# antenna_tracker.net
KiCad netlist of a schematic drawn in EAGLE
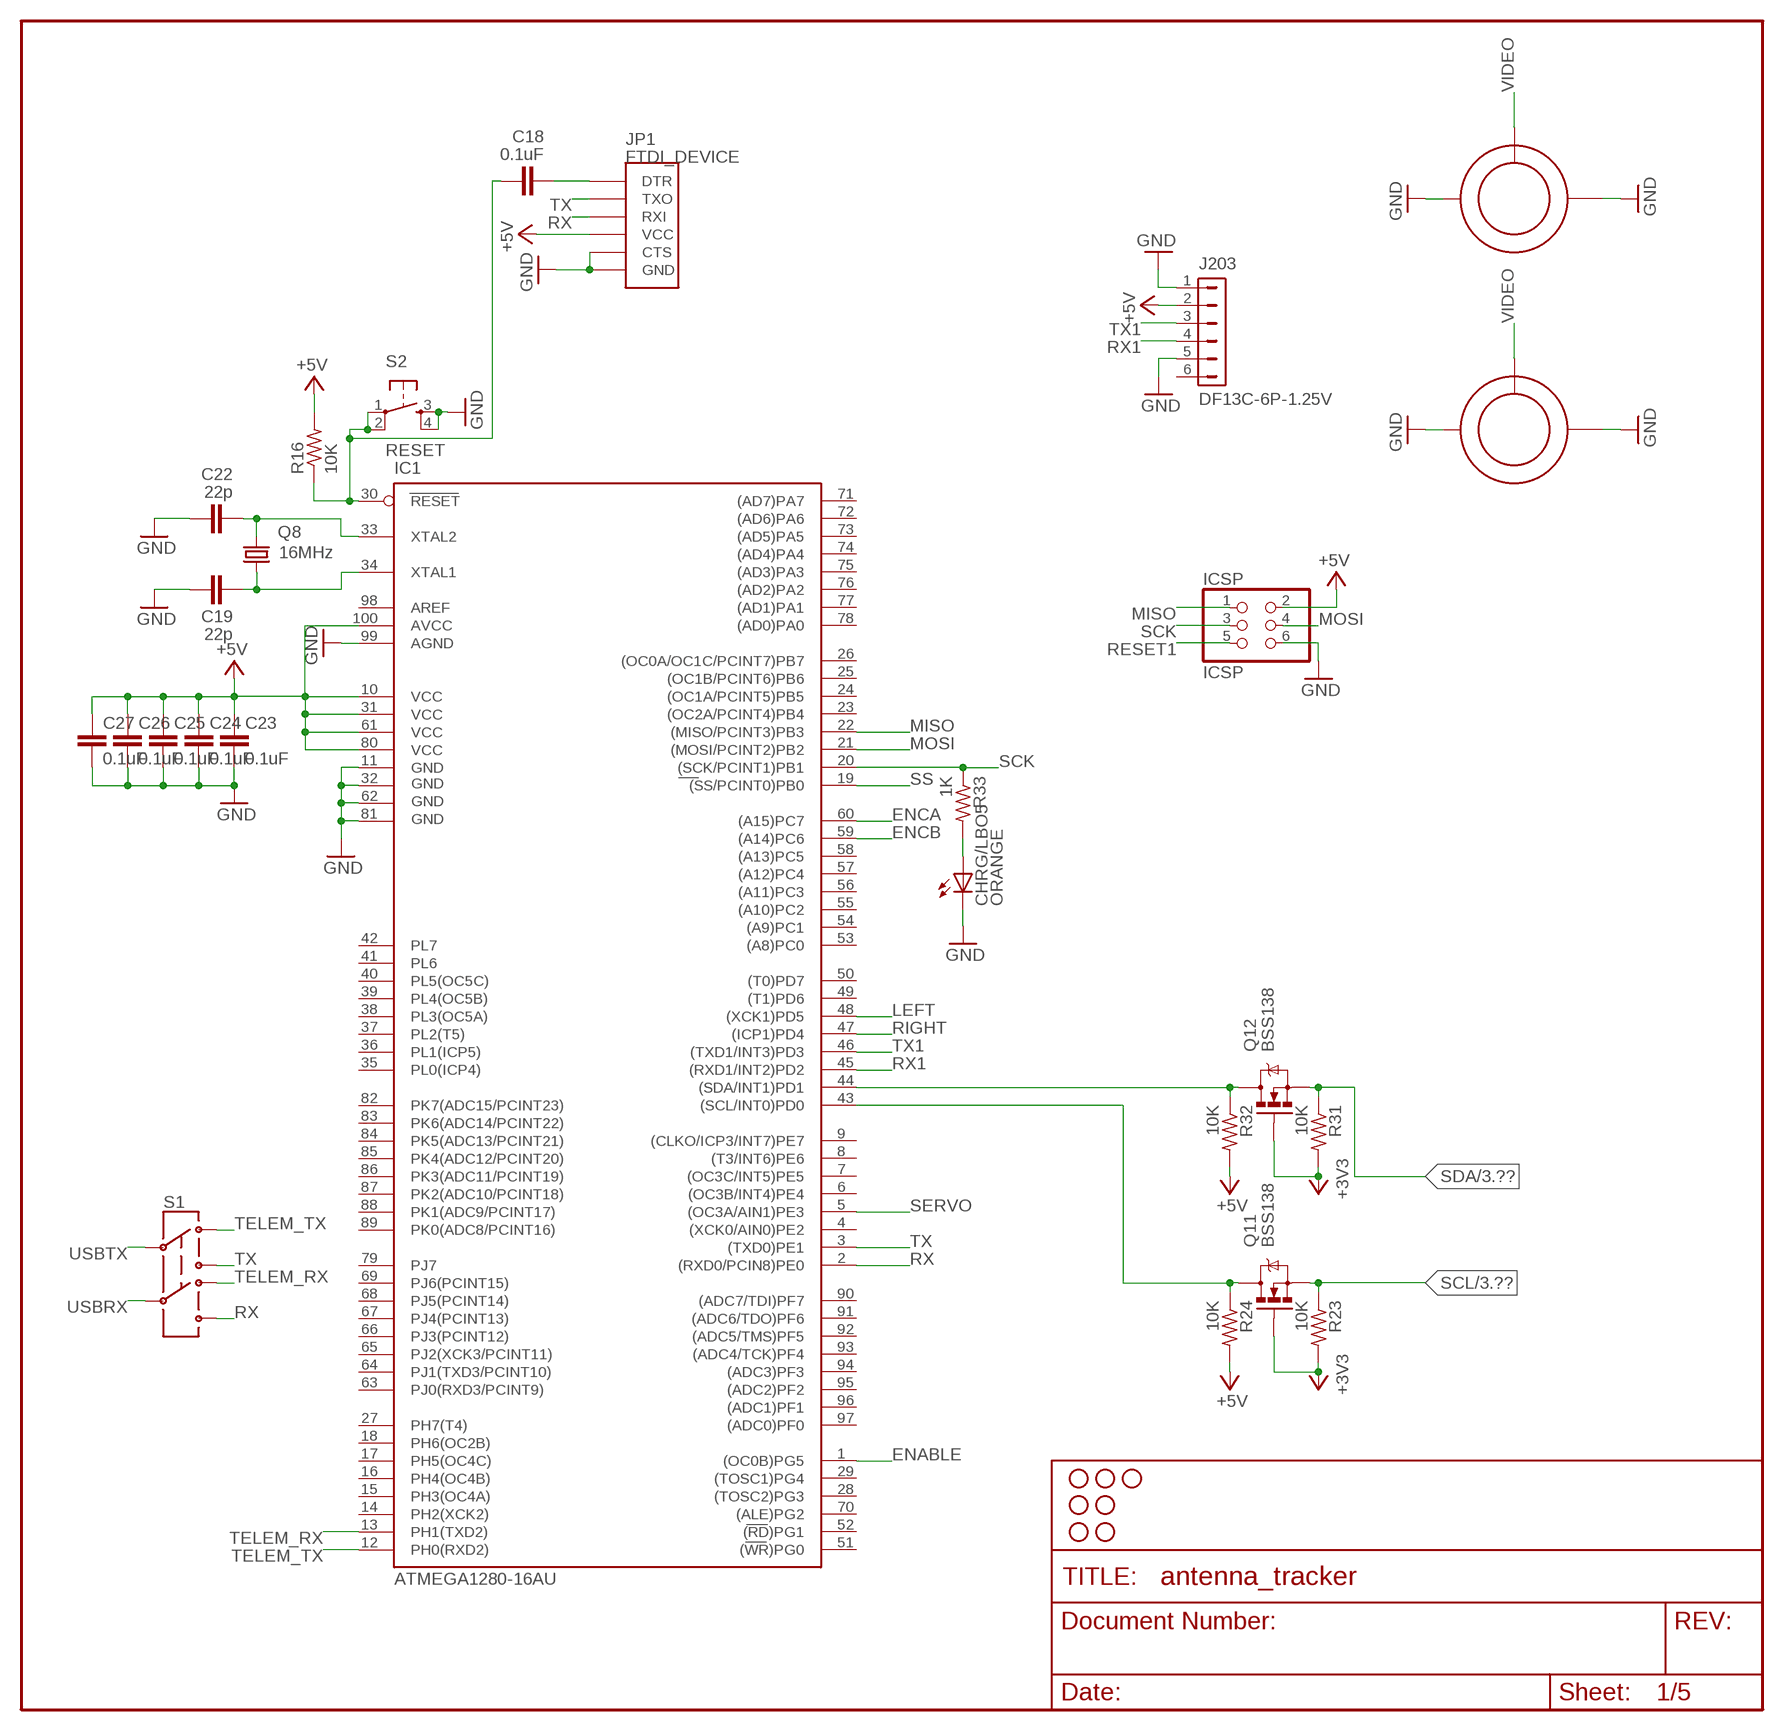
[diagram p0: schematic, sheet 1]
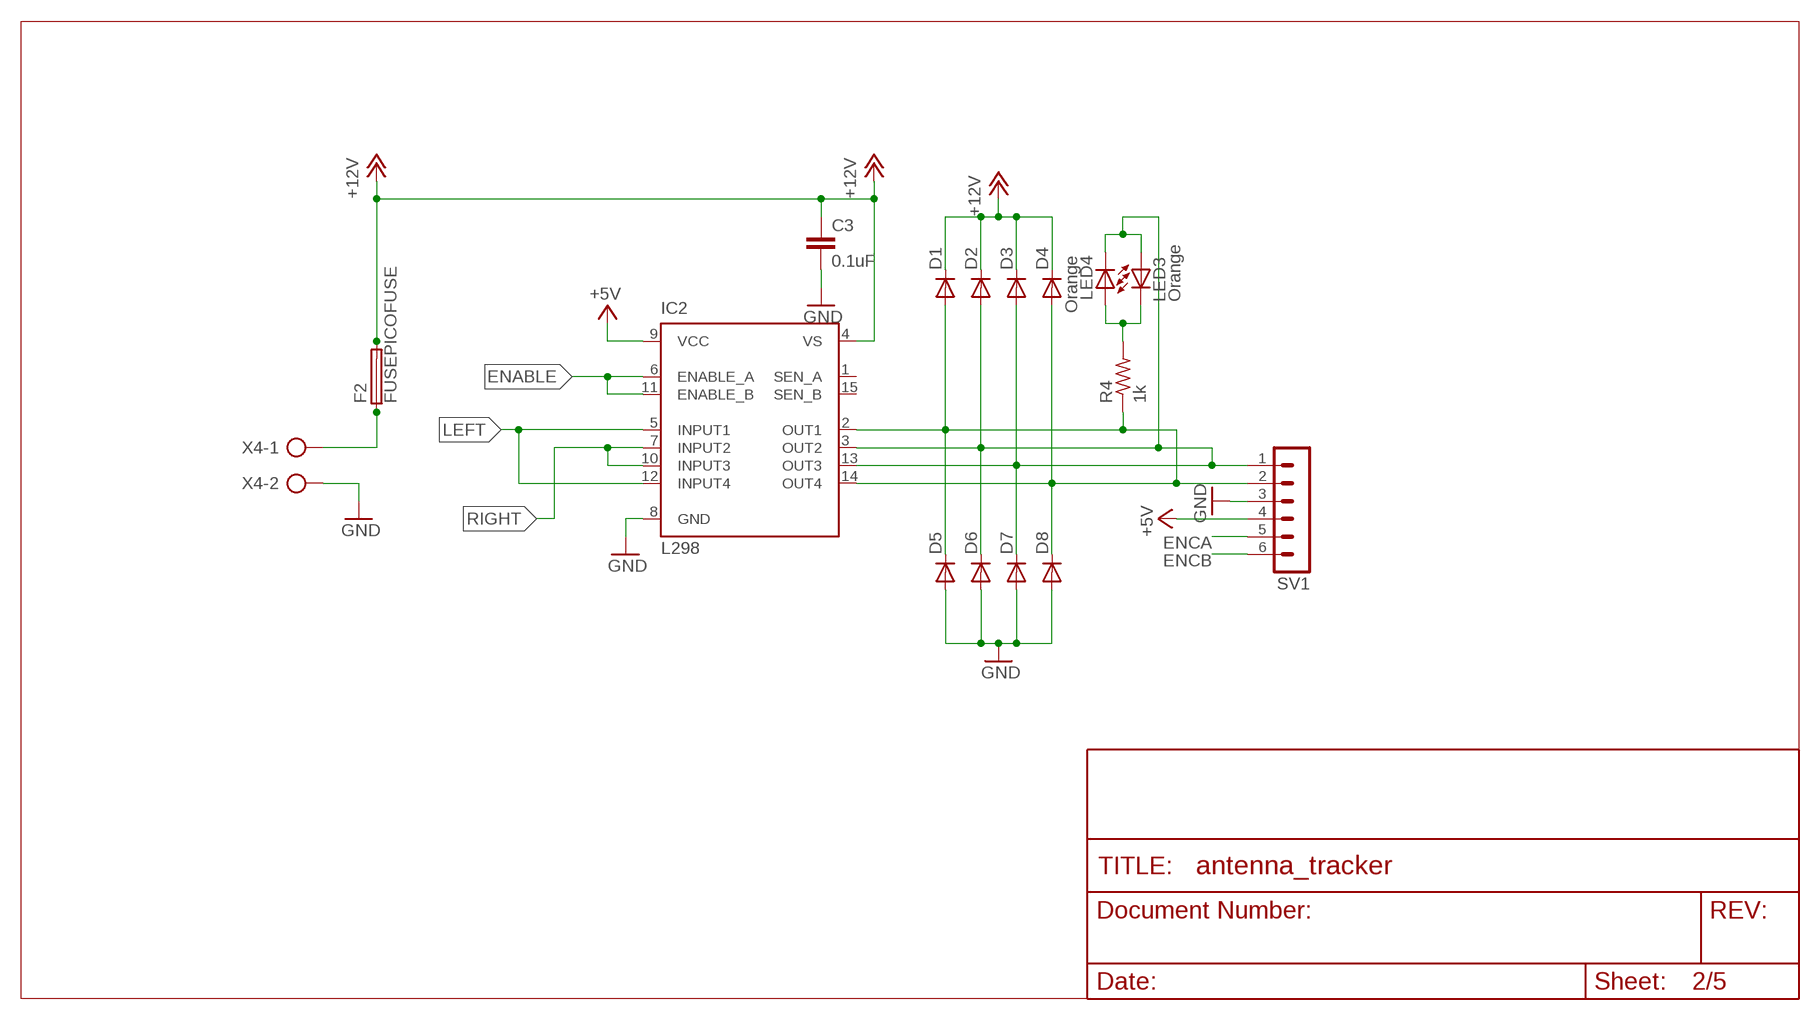
[diagram p1: schematic, sheet 2]
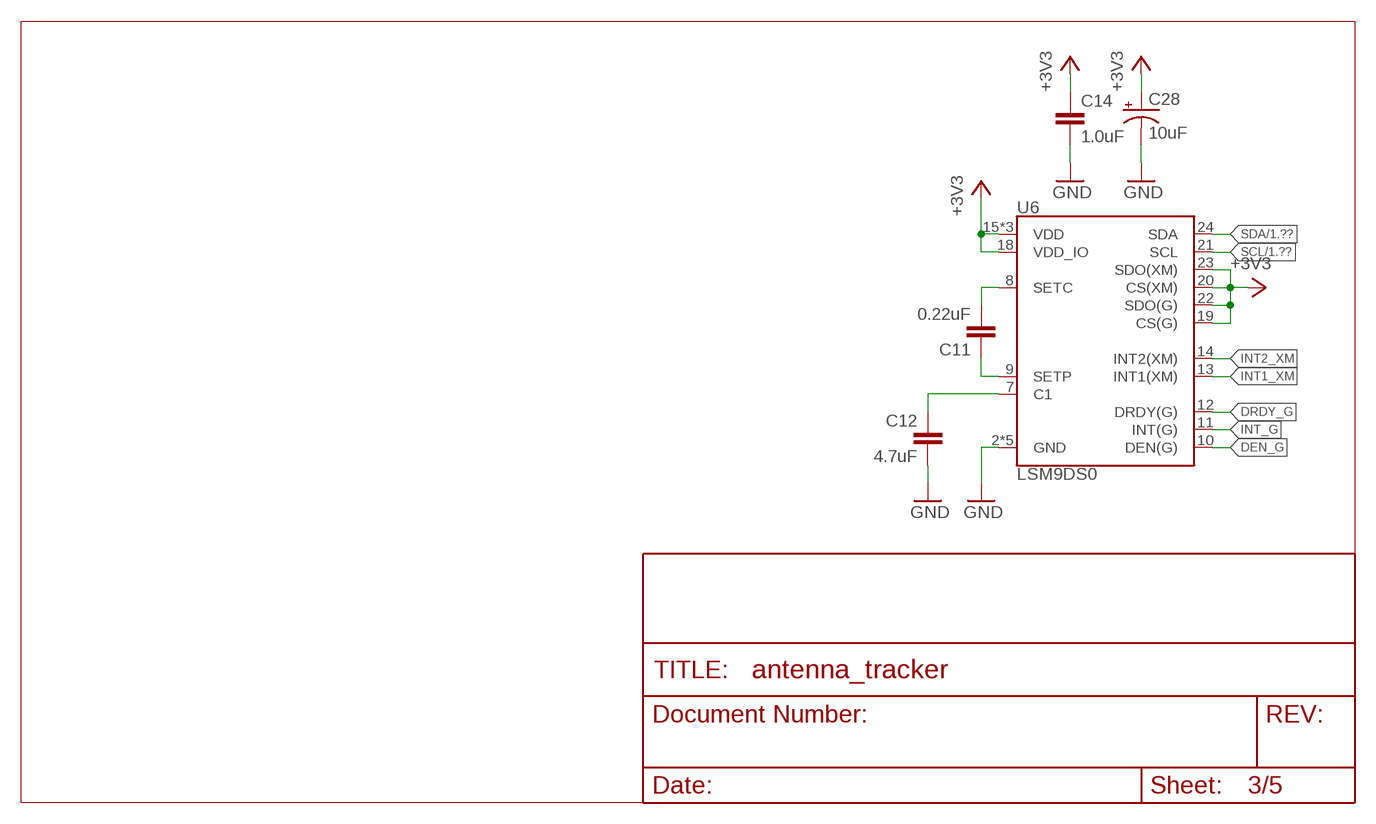
[diagram p2: schematic, sheet 3]
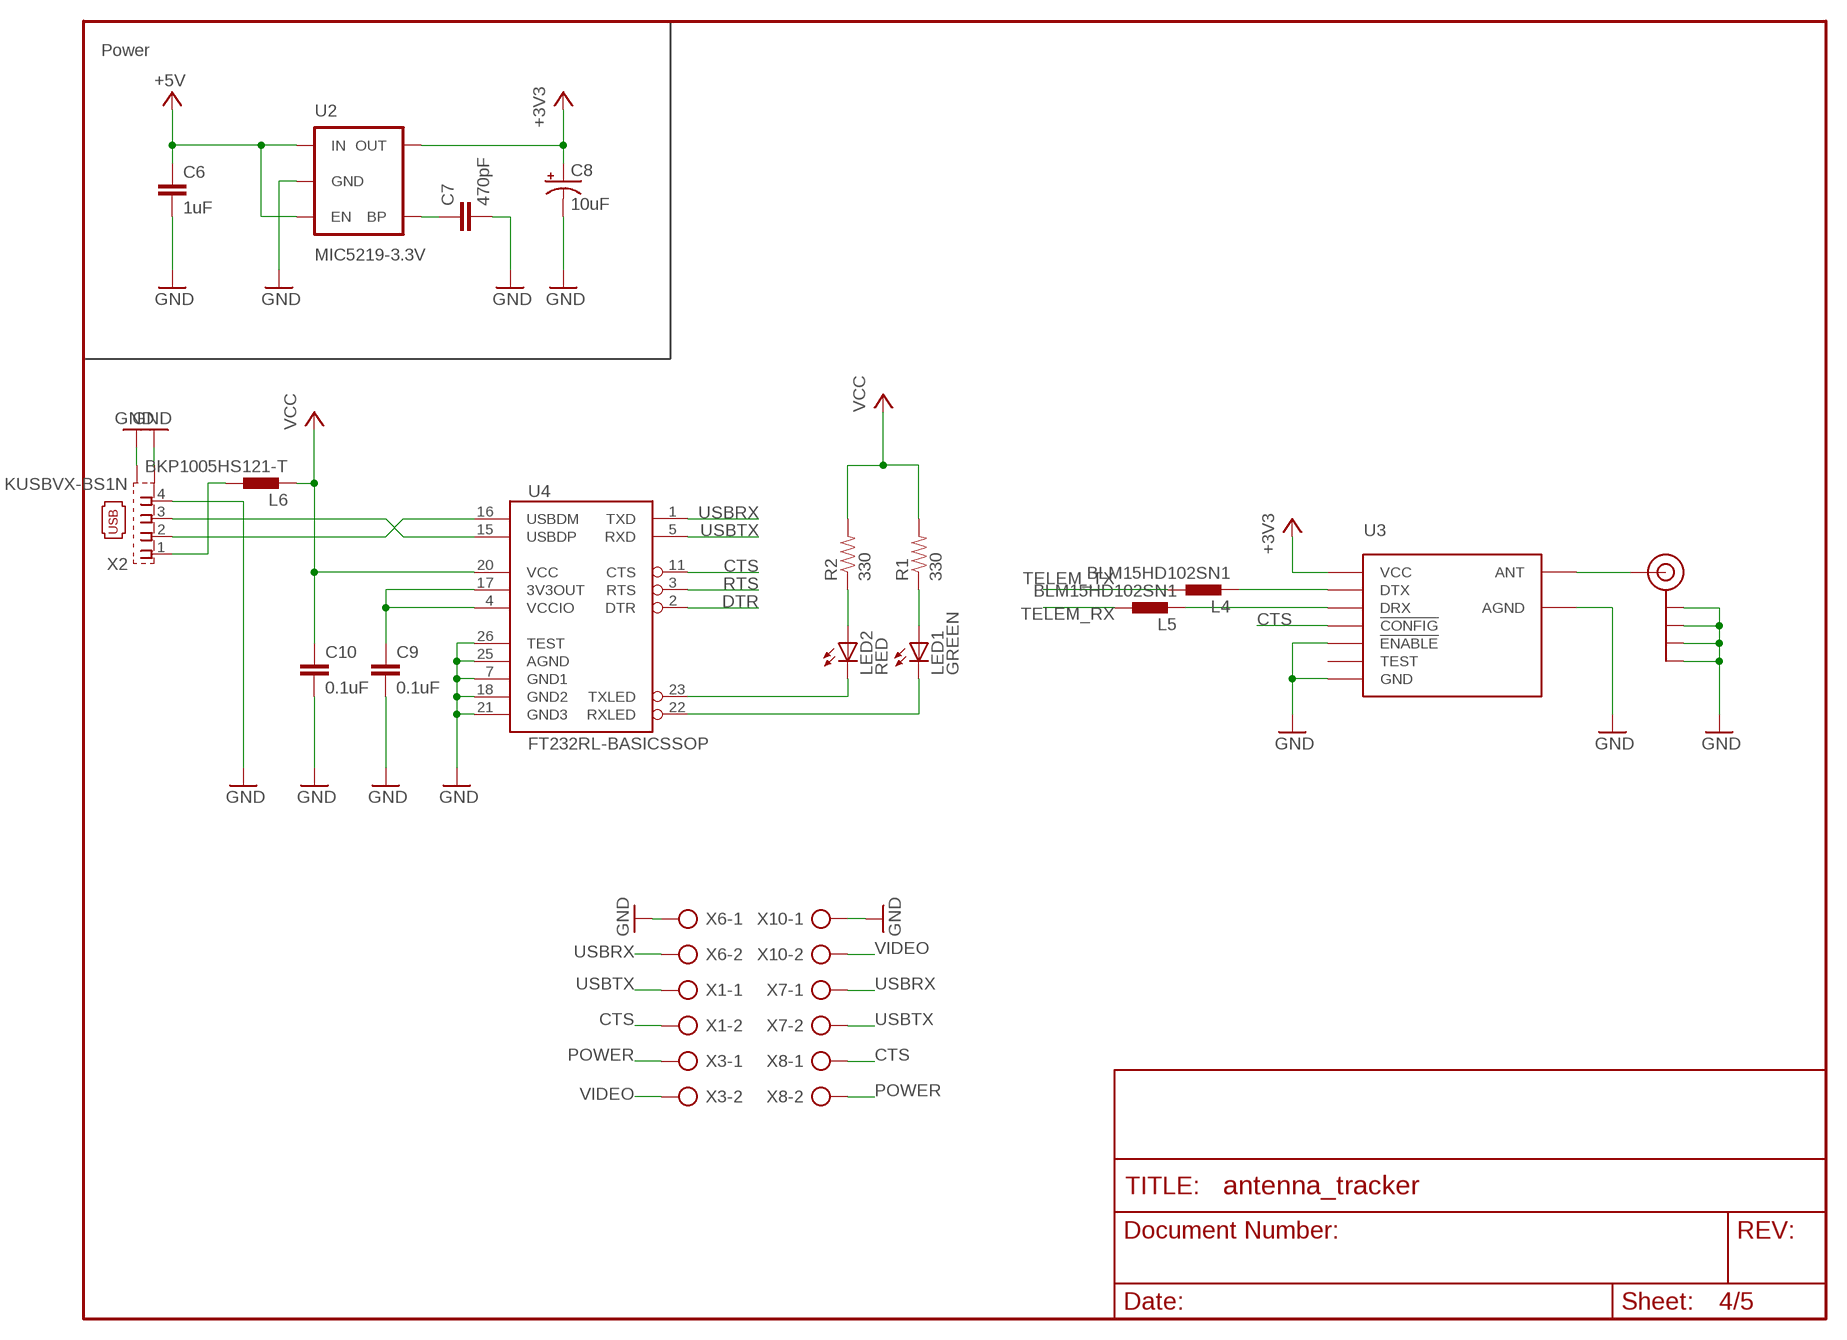
[diagram p3: schematic, sheet 4]
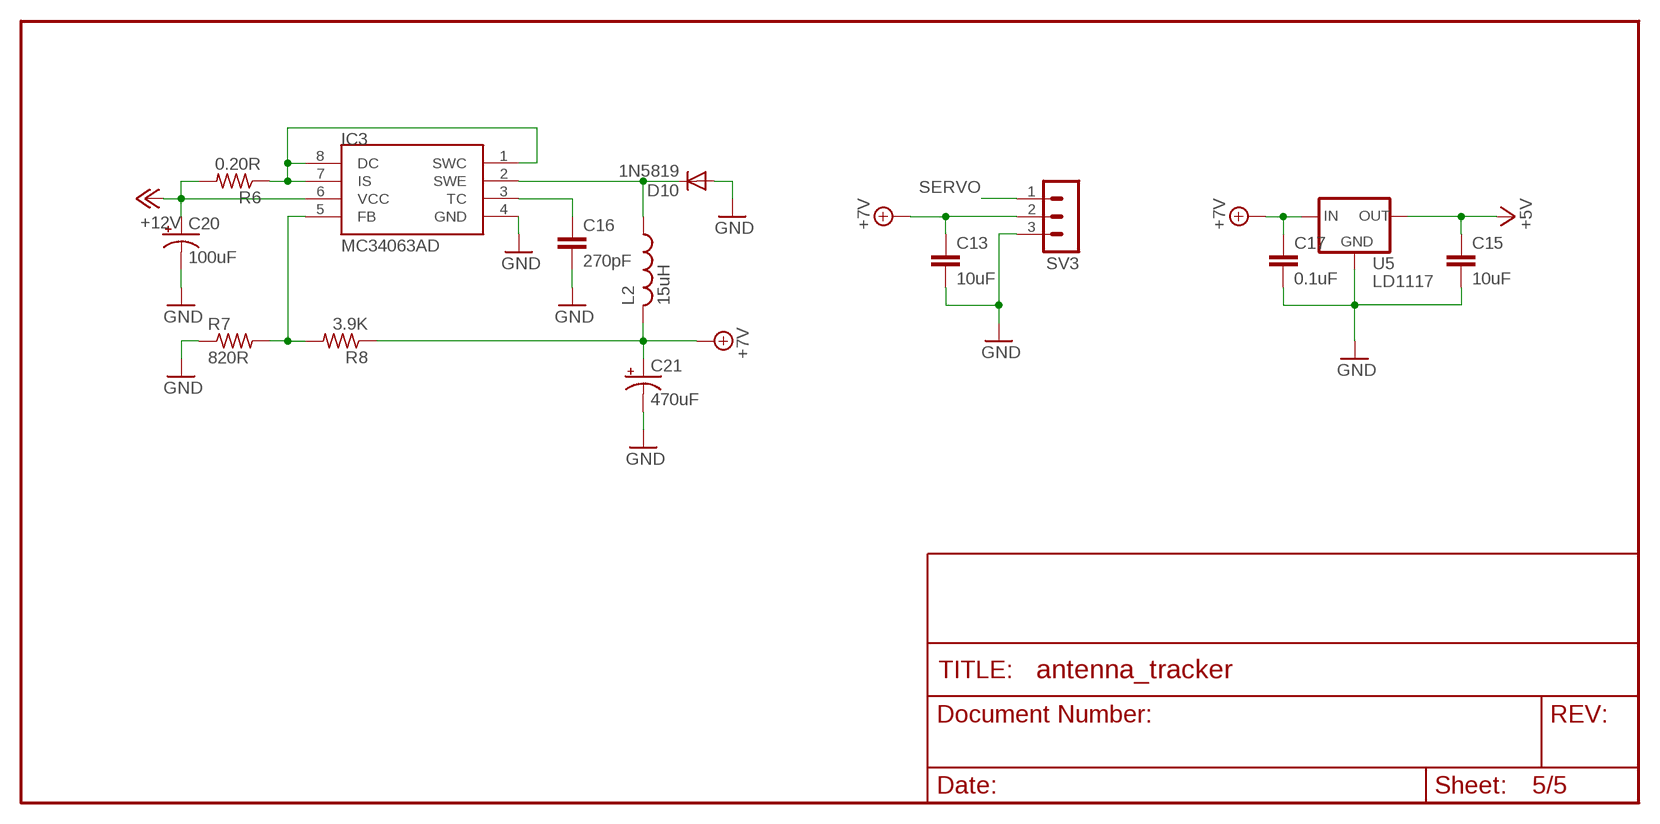
[diagram p4: schematic, sheet 5]

(export (version "E")
  (design (tool "Eeschema 10.0.6"))
  (components
    (comp (ref "C13")
      (value "10uF")
      (footprint "eagle-import:C0805K")
      (fields (field (name "PARTNO") "CL21A106KAFN3NE"))
      (libsource (lib "eagle-import") (part "C-EUC0805K"))
    )
    (comp (ref "C15")
      (value "10uF")
      (footprint "eagle-import:C0805K")
      (fields (field (name "PARTNO") "CL21A106KAFN3NE"))
      (libsource (lib "eagle-import") (part "C-EUC0805K"))
    )
    (comp (ref "C16")
      (value "270pF")
      (footprint "eagle-import:C0603K")
      (fields (field (name "PARTNO") "CC0603KRX7R9BB271"))
      (libsource (lib "eagle-import") (part "resistor_C-EUC0603K"))
    )
    (comp (ref "C17")
      (value "0.1uF")
      (footprint "eagle-import:C0603K")
      (fields (field (name "PARTNO") "GRM188R71E104KA01D"))
      (libsource (lib "eagle-import") (part "C-EUC0603K"))
    )
    (comp (ref "C20")
      (value "100uF")
      (footprint "eagle-import:E2,5-6E")
      (fields (field (name "PARTNO") "ESK107M025AE3AA"))
      (libsource (lib "eagle-import") (part "CPOL-USE2,5-6E"))
    )
    (comp (ref "C21")
      (value "470uF")
      (footprint "eagle-import:E3,5-8")
      (fields (field (name "PARTNO") "UVR1C471MPD"))
      (libsource (lib "eagle-import") (part "CPOL-USE3.5-8"))
    )
    (comp (ref "D10")
      (value "1N5819")
      (footprint "eagle-import:SOD123")
      (fields (field (name "PARTNO") "1N5819HW-7-F"))
      (libsource (lib "eagle-import") (part "DIODE-SOD123"))
    )
    (comp (ref "IC3")
      (value "MC34063AD")
      (footprint "eagle-import:SOIC8")
      (fields (field (name "PARTNO") "MC34063ECD-TR"))
      (libsource (lib "eagle-import") (part "MC34063AD"))
    )
    (comp (ref "L2")
      (value "15uH")
      (footprint "eagle-import:POWER-CHOKE_WE-TPC")
      (fields (field (name "PARTNO") "NR6028T150M"))
      (libsource (lib "eagle-import") (part "L-USWE-TPC"))
    )
    (comp (ref "R6")
      (value "0.20R")
      (footprint "eagle-import:R0603")
      (fields (field (name "PARTNO") "73L2R20J"))
      (libsource (lib "eagle-import") (part "rcl_R-US_R0603"))
    )
    (comp (ref "R7")
      (value "820R")
      (footprint "eagle-import:R0603")
      (fields (field (name "PARTNO") "1623097-1"))
      (libsource (lib "eagle-import") (part "resistor_R-US_R0603"))
    )
    (comp (ref "R8")
      (value "3.9K")
      (footprint "eagle-import:R0603")
      (fields (field (name "PARTNO") "RMCF0603JT3K90"))
      (libsource (lib "eagle-import") (part "rcl_R-US_R0603"))
    )
    (comp (ref "SV3")
      (value "MA03-1")
      (footprint "eagle-import:MA03-1")
      (fields (field (name "PARTNO") "PREC040SFAN-RC"))
      (libsource (lib "eagle-import") (part "MA03-1"))
    )
    (comp (ref "U5")
      (value "LD1117")
      (footprint "eagle-import:DPAK")
      (fields (field (name "PARTNO") "LD1117DT50CTR"))
      (libsource (lib "eagle-import") (part "V_REG_MC33269DT"))
    )
    (comp (ref "C11")
      (value "0.22uF")
      (footprint "eagle-import:0603-CAP")
      (fields (field (name "PARTNO") "CL10B224KA8NNNC"))
      (libsource (lib "eagle-import") (part "0.22UF-25V-10%(0603)"))
    )
    (comp (ref "C12")
      (value "4.7uF")
      (footprint "eagle-import:0603-CAP")
      (fields (field (name "PARTNO") "CL10B475KQ8NQNC"))
      (libsource (lib "eagle-import") (part "4.7UF-6.3V-10%(0603)0603"))
    )
    (comp (ref "C14")
      (value "1.0uF")
      (footprint "eagle-import:0603-CAP")
      (fields (field (name "PARTNO") "C0603C105K8PACTU"))
      (libsource (lib "eagle-import") (part "1.0UF-16V-10%(0603)"))
    )
    (comp (ref "C28")
      (value "10uF")
      (footprint "eagle-import:EIA3216")
      (fields (field (name "PARTNO") "EEE-1CA100SR"))
      (libsource (lib "eagle-import") (part "10UF-16V-10%(TANT)"))
    )
    (comp (ref "U6")
      (value "LSM9DS0")
      (footprint "eagle-import:LGA-24")
      (libsource (lib "eagle-import") (part "LSM9DS0"))
    )
    (comp (ref "C18")
      (value "0.1uF")
      (footprint "eagle-import:C0603K")
      (fields (field (name "PARTNO") "GRM188R71E104KA01D"))
      (libsource (lib "eagle-import") (part "C-EUC0603K"))
    )
    (comp (ref "C19")
      (value "22p")
      (footprint "eagle-import:C0603K")
      (fields (field (name "PARTNO") "C0805C220J5GACTU"))
      (libsource (lib "eagle-import") (part "C-EUC0603K"))
    )
    (comp (ref "C22")
      (value "22p")
      (footprint "eagle-import:C0603K")
      (fields (field (name "PARTNO") "C0805C220J5GACTU"))
      (libsource (lib "eagle-import") (part "C-EUC0603K"))
    )
    (comp (ref "C23")
      (value "0.1uF")
      (footprint "eagle-import:C0603K")
      (fields (field (name "PARTNO") "GRM188R71E104KA01D"))
      (libsource (lib "eagle-import") (part "C-EUC0603K"))
    )
    (comp (ref "C24")
      (value "0.1uF")
      (footprint "eagle-import:C0603K")
      (fields (field (name "PARTNO") "GRM188R71E104KA01D"))
      (libsource (lib "eagle-import") (part "C-EUC0603K"))
    )
    (comp (ref "C25")
      (value "0.1uF")
      (footprint "eagle-import:C0603K")
      (fields (field (name "PARTNO") "GRM188R71E104KA01D"))
      (libsource (lib "eagle-import") (part "C-EUC0603K"))
    )
    (comp (ref "C26")
      (value "0.1uF")
      (footprint "eagle-import:C0603K")
      (fields (field (name "PARTNO") "GRM188R71E104KA01D"))
      (libsource (lib "eagle-import") (part "C-EUC0603K"))
    )
    (comp (ref "C27")
      (value "0.1uF")
      (footprint "eagle-import:C0603K")
      (fields (field (name "PARTNO") "GRM188R71E104KA01D"))
      (libsource (lib "eagle-import") (part "C-EUC0603K"))
    )
    (comp (ref "CHRG/LBO5")
      (value "ORANGE")
      (footprint "eagle-import:CHIP-LED0805")
      (fields (field (name "PARTNO") "APT2012SECK"))
      (libsource (lib "eagle-import") (part "LEDCHIP-LED0805"))
    )
    (comp (ref "IC1")
      (value "ATMEGA1280-16AU")
      (footprint "eagle-import:TQFP100")
      (libsource (lib "eagle-import") (part "ATMEGAAU1280-16"))
    )
    (comp (ref "ICSP")
      (value "ICSP")
      (footprint "eagle-import:2X03")
      (fields (field (name "PARTNO") "PPTC032LFBN-RC"))
      (libsource (lib "eagle-import") (part "PINHD-2X3"))
    )
    (comp (ref "J203")
      (value "DF13C-6P-1.25V")
      (footprint "eagle-import:DF13C-6P-1.25V")
      (fields (field (name "PARTNO") "DF13C-6P-1.25V(20)"))
      (libsource (lib "eagle-import") (part "DF13-6P-1.25V"))
    )
    (comp (ref "JP1")
      (value "FTDI_DEVICE")
      (footprint "eagle-import:FTDI_DEVICE_SIDE")
      (fields (field (name "PARTNO") "PREC040SFAN-RC"))
      (libsource (lib "eagle-import") (part "FTDI_DEVICE"))
    )
    (comp (ref "Q8")
      (value "16MHz")
      (footprint "eagle-import:HC49_S")
      (fields (field (name "PARTNO") "ATS16B"))
      (libsource (lib "eagle-import") (part "CRYTALHC49S"))
    )
    (comp (ref "Q11")
      (value "BSS138")
      (footprint "eagle-import:SOT23-3")
      (libsource (lib "eagle-import") (part "BSS138TRANS-00830"))
    )
    (comp (ref "Q12")
      (value "BSS138")
      (footprint "eagle-import:SOT23-3")
      (libsource (lib "eagle-import") (part "BSS138TRANS-00830"))
    )
    (comp (ref "R16")
      (value "10K")
      (footprint "eagle-import:R0805")
      (fields (field (name "PARTNO") "1623097-1"))
      (libsource (lib "eagle-import") (part "R-US_R0805"))
    )
    (comp (ref "R23")
      (value "10K")
      (footprint "eagle-import:R0805")
      (fields (field (name "PARTNO") "1623097-1"))
      (libsource (lib "eagle-import") (part "R-US_R0805"))
    )
    (comp (ref "R24")
      (value "10K")
      (footprint "eagle-import:R0805")
      (fields (field (name "PARTNO") "1623097-1"))
      (libsource (lib "eagle-import") (part "R-US_R0805"))
    )
    (comp (ref "R31")
      (value "10K")
      (footprint "eagle-import:R0805")
      (fields (field (name "PARTNO") "1623097-1"))
      (libsource (lib "eagle-import") (part "R-US_R0805"))
    )
    (comp (ref "R32")
      (value "10K")
      (footprint "eagle-import:R0805")
      (fields (field (name "PARTNO") "1623097-1"))
      (libsource (lib "eagle-import") (part "R-US_R0805"))
    )
    (comp (ref "R33")
      (value "1K")
      (footprint "eagle-import:M0805")
      (fields (field (name "PARTNO") "RMCF0805JT1K00"))
      (libsource (lib "eagle-import") (part "R-US_M0805"))
    )
    (comp (ref "S1")
      (value "SWITCH-DPDTPTH")
      (footprint "eagle-import:MSS22")
      (fields (field (name "PARTNO") "1825261-2"))
      (libsource (lib "eagle-import") (part "SWITCH-DPDTPTH"))
    )
    (comp (ref "S2")
      (value "RESET")
      (footprint "eagle-import:TACTILE-PTH")
      (fields (field (name "PARTNO") "1825910-6"))
      (libsource (lib "eagle-import") (part "TAC_SWITCHPTH"))
    )
    (comp (ref "STANDOFF1")
      (value "STAND-OFF")
      (footprint "eagle-import:STAND-OFF")
      (libsource (lib "eagle-import") (part "STAND-OFF"))
    )
    (comp (ref "STANDOFF2")
      (value "STAND-OFF")
      (footprint "eagle-import:STAND-OFF")
      (libsource (lib "eagle-import") (part "STAND-OFF"))
    )
    (comp (ref "STANDOFF3")
      (value "STAND-OFF")
      (footprint "eagle-import:STAND-OFF")
      (libsource (lib "eagle-import") (part "STAND-OFF"))
    )
    (comp (ref "STANDOFF4")
      (value "STAND-OFF")
      (footprint "eagle-import:STAND-OFF")
      (libsource (lib "eagle-import") (part "STAND-OFF"))
    )
    (comp (ref "STANDOFF5")
      (value "STAND-OFF")
      (footprint "eagle-import:STAND-OFF")
      (libsource (lib "eagle-import") (part "STAND-OFF"))
    )
    (comp (ref "STANDOFF6")
      (value "STAND-OFF")
      (footprint "eagle-import:STAND-OFF")
      (libsource (lib "eagle-import") (part "STAND-OFF"))
    )
    (comp (ref "STANDOFF7")
      (value "STAND-OFF")
      (footprint "eagle-import:STAND-OFF")
      (libsource (lib "eagle-import") (part "STAND-OFF"))
    )
    (comp (ref "U$10")
      (value "RCA_VERTICAL")
      (footprint "eagle-import:RCA_VERTICAL")
      (fields (field (name "PARTNO") "RCJ-021"))
      (libsource (lib "eagle-import") (part "RCA_VERTICAL"))
    )
    (comp (ref "U$11")
      (value "RCA_VERTICAL")
      (footprint "eagle-import:RCA_VERTICAL")
      (fields (field (name "PARTNO") "RCJ-021"))
      (libsource (lib "eagle-import") (part "RCA_VERTICAL"))
    )
    (comp (ref "C6")
      (value "1uF")
      (footprint "eagle-import:0402-CAP")
      (fields (field (name "PARTNO") "C0603C105K8PACTU"))
      (libsource (lib "eagle-import") (part "CAP0402-CAP"))
    )
    (comp (ref "C7")
      (value "470pF")
      (footprint "eagle-import:0402-CAP")
      (fields (field (name "PARTNO") "GRM1555C1H471JA01D"))
      (libsource (lib "eagle-import") (part "CAP0402-CAP"))
    )
    (comp (ref "C8")
      (value "10uF")
      (footprint "eagle-import:EIA3216")
      (fields (field (name "PARTNO") "EEE-1CA100SR"))
      (libsource (lib "eagle-import") (part "CAP_POL1206"))
    )
    (comp (ref "C9")
      (value "0.1uF")
      (footprint "eagle-import:C0603K")
      (fields (field (name "PARTNO") "GRM188R71E104KA01D"))
      (libsource (lib "eagle-import") (part "resistor_C-EUC0603K"))
    )
    (comp (ref "C10")
      (value "0.1uF")
      (footprint "eagle-import:C0603K")
      (fields (field (name "PARTNO") "GRM188R71E104KA01D"))
      (libsource (lib "eagle-import") (part "resistor_C-EUC0603K"))
    )
    (comp (ref "J$1")
      (value "SMA_EDGE")
      (footprint "eagle-import:SMA-EDGE")
      (fields (field (name "PARTNO") "0732511150"))
      (libsource (lib "eagle-import") (part "SMA_EDGE"))
    )
    (comp (ref "L4")
      (value "BLM15HD102SN1")
      (footprint "eagle-import:0402-IND")
      (fields (field (name "PARTNO") "BLM15HD102SN1D"))
      (libsource (lib "eagle-import") (part "INDUCTOR-0402"))
    )
    (comp (ref "L5")
      (value "BLM15HD102SN1")
      (footprint "eagle-import:0402-IND")
      (fields (field (name "PARTNO") "BLM15HD102SN1D"))
      (libsource (lib "eagle-import") (part "INDUCTOR-0402"))
    )
    (comp (ref "L6")
      (value "BKP1005HS121-T")
      (footprint "eagle-import:0402-IND")
      (libsource (lib "eagle-import") (part "INDUCTOR-0402"))
    )
    (comp (ref "LED1")
      (value "GREEN")
      (footprint "eagle-import:CHIP-LED0805")
      (fields (field (name "PARTNO") "LG R971-KN-1"))
      (libsource (lib "eagle-import") (part "led_LEDCHIP-LED0805"))
    )
    (comp (ref "LED2")
      (value "RED")
      (footprint "eagle-import:CHIP-LED0805")
      (fields (field (name "PARTNO") "LH R974-LP-1"))
      (libsource (lib "eagle-import") (part "led_LEDCHIP-LED0805"))
    )
    (comp (ref "R1")
      (value "330")
      (footprint "eagle-import:0402-RES")
      (fields (field (name "PARTNO") "MCR01MRTF3300"))
      (libsource (lib "eagle-import") (part "RESISTOR0402-RES"))
    )
    (comp (ref "R2")
      (value "330")
      (footprint "eagle-import:0402-RES")
      (fields (field (name "PARTNO") "MCR01MRTF3300"))
      (libsource (lib "eagle-import") (part "RESISTOR0402-RES"))
    )
    (comp (ref "U2")
      (value "MIC5219-3.3V")
      (footprint "eagle-import:SOT23-5")
      (fields (field (name "PARTNO") "MIC5219-3.3YM5 TR"))
      (libsource (lib "eagle-import") (part "V_REG_LDOSMD"))
    )
    (comp (ref "U3")
      (value "HM-TRPSMD")
      (footprint "eagle-import:HM-TRP-SMD")
      (libsource (lib "eagle-import") (part "HM-TRPSMD"))
    )
    (comp (ref "U4")
      (value "FT232RL-BASICSSOP")
      (footprint "eagle-import:SSOP28DB")
      (fields (field (name "PARTNO") "FT232RL-REEL"))
      (libsource (lib "eagle-import") (part "FT232RL-BASICSSOP"))
    )
    (comp (ref "X1")
      (value "AK300/2")
      (footprint "eagle-import:AK300_2")
      (fields (field (name "PARTNO") "OSTTC022162"))
      (libsource (lib "eagle-import") (part "AK300/2"))
    )
    (comp (ref "X2")
      (value "KUSBVX-BS1N")
      (footprint "eagle-import:KUSBVX-BS1N")
      (fields (field (name "PARTNO") "5787834-1"))
      (libsource (lib "eagle-import") (part "KUSBVX-BS1N"))
    )
    (comp (ref "X3")
      (value "AK300/2")
      (footprint "eagle-import:AK300_2")
      (fields (field (name "PARTNO") "OSTTC022162"))
      (libsource (lib "eagle-import") (part "AK300/2"))
    )
    (comp (ref "X6")
      (value "AK300/2")
      (footprint "eagle-import:AK300_2")
      (fields (field (name "PARTNO") "OSTTC022162"))
      (libsource (lib "eagle-import") (part "AK300/2"))
    )
    (comp (ref "X7")
      (value "AK300/2")
      (footprint "eagle-import:AK300_2")
      (fields (field (name "PARTNO") "OSTTC022162"))
      (libsource (lib "eagle-import") (part "AK300/2"))
    )
    (comp (ref "X8")
      (value "AK300/2")
      (footprint "eagle-import:AK300_2")
      (fields (field (name "PARTNO") "OSTTC022162"))
      (libsource (lib "eagle-import") (part "AK300/2"))
    )
    (comp (ref "X10")
      (value "AK300/2")
      (footprint "eagle-import:AK300_2")
      (fields (field (name "PARTNO") "OSTTC022162"))
      (libsource (lib "eagle-import") (part "AK300/2"))
    )
    (comp (ref "C3")
      (value "0.1uF")
      (footprint "eagle-import:0603-CAP")
      (fields (field (name "PARTNO") "GRM188R71E104KA01D") (field (name "PROD_ID") "CAP-08390"))
      (libsource (lib "eagle-import") (part "0.1UF-100V-10%(0603)"))
    )
    (comp (ref "D1")
      (value "DIODE-DO214AC")
      (footprint "eagle-import:DO214AC")
      (fields (field (name "PARTNO") "ES2B-LTP"))
      (libsource (lib "eagle-import") (part "DIODE-DO214AC"))
    )
    (comp (ref "D2")
      (value "DIODE-DO214AC")
      (footprint "eagle-import:DO214AC")
      (fields (field (name "PARTNO") "ES2B-LTP"))
      (libsource (lib "eagle-import") (part "DIODE-DO214AC"))
    )
    (comp (ref "D3")
      (value "DIODE-DO214AC")
      (footprint "eagle-import:DO214AC")
      (fields (field (name "PARTNO") "ES2B-LTP"))
      (libsource (lib "eagle-import") (part "DIODE-DO214AC"))
    )
    (comp (ref "D4")
      (value "DIODE-DO214AC")
      (footprint "eagle-import:DO214AC")
      (fields (field (name "PARTNO") "ES2B-LTP"))
      (libsource (lib "eagle-import") (part "DIODE-DO214AC"))
    )
    (comp (ref "D5")
      (value "DIODE-DO214AC")
      (footprint "eagle-import:DO214AC")
      (fields (field (name "PARTNO") "ES2B-LTP"))
      (libsource (lib "eagle-import") (part "DIODE-DO214AC"))
    )
    (comp (ref "D6")
      (value "DIODE-DO214AC")
      (footprint "eagle-import:DO214AC")
      (fields (field (name "PARTNO") "ES2B-LTP"))
      (libsource (lib "eagle-import") (part "DIODE-DO214AC"))
    )
    (comp (ref "D7")
      (value "DIODE-DO214AC")
      (footprint "eagle-import:DO214AC")
      (fields (field (name "PARTNO") "ES2B-LTP"))
      (libsource (lib "eagle-import") (part "DIODE-DO214AC"))
    )
    (comp (ref "D8")
      (value "DIODE-DO214AC")
      (footprint "eagle-import:DO214AC")
      (fields (field (name "PARTNO") "ES2B-LTP"))
      (libsource (lib "eagle-import") (part "DIODE-DO214AC"))
    )
    (comp (ref "F2")
      (value "FUSEPICOFUSE")
      (footprint "eagle-import:PICOFUSE")
      (fields (field (name "PARTNO") "RUEF700-2"))
      (libsource (lib "eagle-import") (part "FUSEPICOFUSE"))
    )
    (comp (ref "IC2")
      (value "L298")
      (footprint "eagle-import:MULTIWATT-15")
      (fields (field (name "MPN") "L298N"))
      (libsource (lib "eagle-import") (part "L298"))
    )
    (comp (ref "LED3")
      (value "Orange")
      (footprint "eagle-import:SML0805")
      (fields (field (name "PARTNO") "APT2012SECK"))
      (libsource (lib "eagle-import") (part "LEDSML0805"))
    )
    (comp (ref "LED4")
      (value "Orange")
      (footprint "eagle-import:SML0805")
      (fields (field (name "PARTNO") "APT2012SECK"))
      (libsource (lib "eagle-import") (part "LEDSML0805"))
    )
    (comp (ref "R4")
      (value "1k")
      (footprint "eagle-import:R0805")
      (fields (field (name "PARTNO") "RMCF0805JT1K00"))
      (libsource (lib "eagle-import") (part "resistor_R-US_R0805"))
    )
    (comp (ref "SV1")
      (value "MA06-1")
      (footprint "eagle-import:MA06-1")
      (fields (field (name "PARTNO") "PREC040SFAN-RC"))
      (libsource (lib "eagle-import") (part "MA06-1"))
    )
    (comp (ref "X4")
      (value "AK300/2")
      (footprint "eagle-import:AK300_2")
      (fields (field (name "PARTNO") "OSTTC022162"))
      (libsource (lib "eagle-import") (part "AK300/2"))
    )
  )
  (nets
    (net (code "1") (name "+3V3") (class "Default")
      (node (ref "C14") (pin "1") (pinfunction "1_1") (pintype "passive"))
      (node (ref "C28") (pin "A") (pinfunction "+_A") (pintype "passive"))
      (node (ref "C8") (pin "A") (pinfunction "+_A") (pintype "passive"))
      (node (ref "Q11") (pin "1") (pinfunction "G_1") (pintype "passive"))
      (node (ref "Q12") (pin "1") (pinfunction "G_1") (pintype "passive"))
      (node (ref "R23") (pin "2") (pinfunction "2_2") (pintype "passive"))
      (node (ref "R31") (pin "2") (pinfunction "2_2") (pintype "passive"))
      (node (ref "U2") (pin "5") (pinfunction "OUT_5") (pintype "passive"))
      (node (ref "U3") (pin "VCC") (pinfunction "VCC_VCC") (pintype "power_in"))
      (node (ref "U6") (pin "15") (pinfunction "VDD_15") (pintype "bidirectional"))
      (node (ref "U6") (pin "16") (pinfunction "VDD_16") (pintype "bidirectional"))
      (node (ref "U6") (pin "17") (pinfunction "VDD_17") (pintype "bidirectional"))
      (node (ref "U6") (pin "18") (pinfunction "VDD_IO_18") (pintype "bidirectional"))
      (node (ref "U6") (pin "19") (pinfunction "CS(G)_19") (pintype "bidirectional"))
      (node (ref "U6") (pin "20") (pinfunction "CS(XM)_20") (pintype "bidirectional"))
      (node (ref "U6") (pin "22") (pinfunction "SDO(G)_22") (pintype "bidirectional"))
      (node (ref "U6") (pin "23") (pinfunction "SDO(XM)_23") (pintype "bidirectional"))
    )
    (net (code "2") (name "+5V") (class "Default")
      (node (ref "C15") (pin "1") (pinfunction "1_1") (pintype "passive"))
      (node (ref "C23") (pin "1") (pinfunction "1_1") (pintype "passive"))
      (node (ref "C24") (pin "1") (pinfunction "1_1") (pintype "passive"))
      (node (ref "C25") (pin "1") (pinfunction "1_1") (pintype "passive"))
      (node (ref "C26") (pin "1") (pinfunction "1_1") (pintype "passive"))
      (node (ref "C27") (pin "1") (pinfunction "1_1") (pintype "passive"))
      (node (ref "C6") (pin "1") (pinfunction "1_1") (pintype "passive"))
      (node (ref "IC1") (pin "10") (pinfunction "VCC_10") (pintype "power_in"))
      (node (ref "IC1") (pin "100") (pinfunction "AVCC_100") (pintype "power_in"))
      (node (ref "IC1") (pin "31") (pinfunction "VCC1_31") (pintype "power_in"))
      (node (ref "IC1") (pin "61") (pinfunction "VCC2_61") (pintype "power_in"))
      (node (ref "IC1") (pin "80") (pinfunction "VCC3_80") (pintype "power_in"))
      (node (ref "IC2") (pin "9") (pinfunction "VCC_9") (pintype "power_in"))
      (node (ref "ICSP") (pin "2") (pinfunction "2_2") (pintype "passive"))
      (node (ref "J203") (pin "2") (pinfunction "2_2") (pintype "passive"))
      (node (ref "JP1") (pin "P$4") (pinfunction "VCC_P$4") (pintype "bidirectional"))
      (node (ref "R16") (pin "2") (pinfunction "2_2") (pintype "passive"))
      (node (ref "R24") (pin "2") (pinfunction "2_2") (pintype "passive"))
      (node (ref "R32") (pin "2") (pinfunction "2_2") (pintype "passive"))
      (node (ref "SV1") (pin "4") (pinfunction "4_4") (pintype "passive"))
      (node (ref "U2") (pin "1") (pinfunction "IN_1") (pintype "input"))
      (node (ref "U2") (pin "3") (pinfunction "EN_3") (pintype "input"))
      (node (ref "U5") (pin "4") (pinfunction "OUT_4") (pintype "output"))
    )
    (net (code "3") (name "+7V") (class "Default")
      (node (ref "C13") (pin "1") (pinfunction "1_1") (pintype "passive"))
      (node (ref "C17") (pin "1") (pinfunction "1_1") (pintype "passive"))
      (node (ref "C21") (pin "+") (pinfunction "+_+") (pintype "passive"))
      (node (ref "L2") (pin "2") (pinfunction "2_2") (pintype "passive"))
      (node (ref "R8") (pin "1") (pinfunction "1_1") (pintype "passive"))
      (node (ref "SV3") (pin "2") (pinfunction "2_2") (pintype "passive"))
      (node (ref "U5") (pin "3") (pinfunction "IN_3") (pintype "input"))
    )
    (net (code "4") (name "+12V") (class "Default")
      (node (ref "C20") (pin "+") (pinfunction "+_+") (pintype "passive"))
      (node (ref "C3") (pin "1") (pinfunction "1_1") (pintype "passive"))
      (node (ref "D1") (pin "C") (pinfunction "C_C") (pintype "passive"))
      (node (ref "D2") (pin "C") (pinfunction "C_C") (pintype "passive"))
      (node (ref "D3") (pin "C") (pinfunction "C_C") (pintype "passive"))
      (node (ref "D4") (pin "C") (pinfunction "C_C") (pintype "passive"))
      (node (ref "F2") (pin "2") (pinfunction "2_2") (pintype "passive"))
      (node (ref "IC2") (pin "4") (pinfunction "VS_4") (pintype "power_in"))
      (node (ref "IC3") (pin "6") (pinfunction "VCC_6") (pintype "passive"))
      (node (ref "R6") (pin "2") (pinfunction "2_2") (pintype "passive"))
    )
    (net (code "5") (name "CTS") (class "Default")
      (node (ref "U3") (pin "!CONFIG") (pinfunction "~{CONFIG}_!CONFIG") (pintype "input"))
      (node (ref "U4") (pin "11") (pinfunction "CTS_11") (pintype "bidirectional"))
      (node (ref "X1") (pin "2") (pinfunction "KL_2") (pintype "passive"))
      (node (ref "X8") (pin "1") (pinfunction "KL_1") (pintype "passive"))
    )
    (net (code "6") (name "DEN_G") (class "Default")
      (node (ref "U6") (pin "10") (pinfunction "DEN(G)_10") (pintype "bidirectional"))
    )
    (net (code "7") (name "DRDY_G") (class "Default")
      (node (ref "U6") (pin "12") (pinfunction "DRDY(G)_12") (pintype "bidirectional"))
    )
    (net (code "8") (name "DTR") (class "Default")
      (node (ref "U4") (pin "2") (pinfunction "DTR_2") (pintype "bidirectional"))
    )
    (net (code "9") (name "ENABLE") (class "Default")
      (node (ref "IC1") (pin "1") (pinfunction "(OC0B)PG5_1") (pintype "bidirectional"))
      (node (ref "IC2") (pin "11") (pinfunction "ENABLE_B_11") (pintype "input"))
      (node (ref "IC2") (pin "6") (pinfunction "ENABLE_A_6") (pintype "input"))
    )
    (net (code "10") (name "ENCA") (class "Default")
      (node (ref "IC1") (pin "60") (pinfunction "(A15)PC7_60") (pintype "bidirectional"))
      (node (ref "SV1") (pin "5") (pinfunction "5_5") (pintype "passive"))
    )
    (net (code "11") (name "ENCB") (class "Default")
      (node (ref "IC1") (pin "59") (pinfunction "(A14)PC6_59") (pintype "bidirectional"))
      (node (ref "SV1") (pin "6") (pinfunction "6_6") (pintype "passive"))
    )
    (net (code "12") (name "GND") (class "Default")
      (node (ref "C10") (pin "2") (pinfunction "2_2") (pintype "passive"))
      (node (ref "C12") (pin "2") (pinfunction "2_2") (pintype "passive"))
      (node (ref "C13") (pin "2") (pinfunction "2_2") (pintype "passive"))
      (node (ref "C14") (pin "2") (pinfunction "2_2") (pintype "passive"))
      (node (ref "C15") (pin "2") (pinfunction "2_2") (pintype "passive"))
      (node (ref "C16") (pin "2") (pinfunction "2_2") (pintype "passive"))
      (node (ref "C17") (pin "2") (pinfunction "2_2") (pintype "passive"))
      (node (ref "C19") (pin "1") (pinfunction "1_1") (pintype "passive"))
      (node (ref "C20") (pin "-") (pinfunction "-_-") (pintype "passive"))
      (node (ref "C21") (pin "-") (pinfunction "-_-") (pintype "passive"))
      (node (ref "C22") (pin "1") (pinfunction "1_1") (pintype "passive"))
      (node (ref "C23") (pin "2") (pinfunction "2_2") (pintype "passive"))
      (node (ref "C24") (pin "2") (pinfunction "2_2") (pintype "passive"))
      (node (ref "C25") (pin "2") (pinfunction "2_2") (pintype "passive"))
      (node (ref "C26") (pin "2") (pinfunction "2_2") (pintype "passive"))
      (node (ref "C27") (pin "2") (pinfunction "2_2") (pintype "passive"))
      (node (ref "C28") (pin "C") (pinfunction "-_C") (pintype "passive"))
      (node (ref "C3") (pin "2") (pinfunction "2_2") (pintype "passive"))
      (node (ref "C6") (pin "2") (pinfunction "2_2") (pintype "passive"))
      (node (ref "C7") (pin "2") (pinfunction "2_2") (pintype "passive"))
      (node (ref "C8") (pin "C") (pinfunction "-_C") (pintype "passive"))
      (node (ref "C9") (pin "2") (pinfunction "2_2") (pintype "passive"))
      (node (ref "CHRG/LBO5") (pin "C") (pinfunction "C_C") (pintype "passive"))
      (node (ref "D10") (pin "A") (pinfunction "A_A") (pintype "passive"))
      (node (ref "D5") (pin "A") (pinfunction "A_A") (pintype "passive"))
      (node (ref "D6") (pin "A") (pinfunction "A_A") (pintype "passive"))
      (node (ref "D7") (pin "A") (pinfunction "A_A") (pintype "passive"))
      (node (ref "D8") (pin "A") (pinfunction "A_A") (pintype "passive"))
      (node (ref "IC1") (pin "11") (pinfunction "GND_11") (pintype "power_in"))
      (node (ref "IC1") (pin "32") (pinfunction "GND1_32") (pintype "power_in"))
      (node (ref "IC1") (pin "62") (pinfunction "GND2_62") (pintype "power_in"))
      (node (ref "IC1") (pin "81") (pinfunction "GND3_81") (pintype "power_in"))
      (node (ref "IC1") (pin "99") (pinfunction "AGND_99") (pintype "power_in"))
      (node (ref "IC2") (pin "8") (pinfunction "GND_8") (pintype "power_in"))
      (node (ref "IC3") (pin "4") (pinfunction "GND_4") (pintype "passive"))
      (node (ref "ICSP") (pin "6") (pinfunction "6_6") (pintype "passive"))
      (node (ref "J$1") (pin "GND@0") (pinfunction "GND_GND@0") (pintype "bidirectional"))
      (node (ref "J$1") (pin "GND@1") (pinfunction "GND_GND@1") (pintype "bidirectional"))
      (node (ref "J$1") (pin "GND@2") (pinfunction "GND_GND@2") (pintype "bidirectional"))
      (node (ref "J$1") (pin "GND@3") (pinfunction "GND_GND@3") (pintype "bidirectional"))
      (node (ref "J203") (pin "1") (pinfunction "1_1") (pintype "passive"))
      (node (ref "J203") (pin "5") (pinfunction "5_5") (pintype "passive"))
      (node (ref "JP1") (pin "P$5") (pinfunction "CTS_P$5") (pintype "bidirectional"))
      (node (ref "JP1") (pin "P$6") (pinfunction "GND_P$6") (pintype "bidirectional"))
      (node (ref "R7") (pin "1") (pinfunction "1_1") (pintype "passive"))
      (node (ref "S2") (pin "3") (pinfunction "3_3") (pintype "passive"))
      (node (ref "S2") (pin "4") (pinfunction "4_4") (pintype "passive"))
      (node (ref "SV1") (pin "3") (pinfunction "3_3") (pintype "passive"))
      (node (ref "SV3") (pin "3") (pinfunction "3_3") (pintype "passive"))
      (node (ref "U$10") (pin "P$1") (pinfunction "GND_P$1") (pintype "bidirectional"))
      (node (ref "U$10") (pin "P$2") (pinfunction "GND_P$2") (pintype "bidirectional"))
      (node (ref "U$11") (pin "P$1") (pinfunction "GND_P$1") (pintype "bidirectional"))
      (node (ref "U$11") (pin "P$2") (pinfunction "GND_P$2") (pintype "bidirectional"))
      (node (ref "U2") (pin "2") (pinfunction "GND_2") (pintype "input"))
      (node (ref "U3") (pin "!ENABLE") (pinfunction "~{ENABLE}_!ENABLE") (pintype "input"))
      (node (ref "U3") (pin "AGND") (pinfunction "AGND_AGND") (pintype "power_in"))
      (node (ref "U3") (pin "GND") (pinfunction "GND_GND") (pintype "power_in"))
      (node (ref "U4") (pin "18") (pinfunction "GND2_18") (pintype "power_in"))
      (node (ref "U4") (pin "21") (pinfunction "GND3_21") (pintype "power_in"))
      (node (ref "U4") (pin "25") (pinfunction "AGND_25") (pintype "power_in"))
      (node (ref "U4") (pin "26") (pinfunction "TEST_26") (pintype "input"))
      (node (ref "U4") (pin "7") (pinfunction "GND1_7") (pintype "power_in"))
      (node (ref "U5") (pin "1") (pinfunction "GND_1") (pintype "input"))
      (node (ref "U6") (pin "2") (pinfunction "GND_2") (pintype "bidirectional"))
      (node (ref "U6") (pin "3") (pinfunction "GND_3") (pintype "bidirectional"))
      (node (ref "U6") (pin "4") (pinfunction "GND_4") (pintype "bidirectional"))
      (node (ref "U6") (pin "5") (pinfunction "GND_5") (pintype "bidirectional"))
      (node (ref "U6") (pin "6") (pinfunction "GND_6") (pintype "bidirectional"))
      (node (ref "X10") (pin "1") (pinfunction "KL_1") (pintype "passive"))
      (node (ref "X2") (pin "4") (pinfunction "4_4") (pintype "passive"))
      (node (ref "X2") (pin "M1") (pinfunction "S1_M1") (pintype "passive"))
      (node (ref "X2") (pin "M2") (pinfunction "S2_M2") (pintype "passive"))
      (node (ref "X4") (pin "2") (pinfunction "KL_2") (pintype "passive"))
      (node (ref "X6") (pin "1") (pinfunction "KL_1") (pintype "passive"))
    )
    (net (code "13") (name "INT1_XM") (class "Default")
      (node (ref "U6") (pin "13") (pinfunction "INT1(XM)_13") (pintype "bidirectional"))
    )
    (net (code "14") (name "INT2_XM") (class "Default")
      (node (ref "U6") (pin "14") (pinfunction "INT2(XM)_14") (pintype "bidirectional"))
    )
    (net (code "15") (name "INT_G") (class "Default")
      (node (ref "U6") (pin "11") (pinfunction "INT(G)_11") (pintype "bidirectional"))
    )
    (net (code "16") (name "LEFT") (class "Default")
      (node (ref "IC1") (pin "48") (pinfunction "(XCK1)PD5_48") (pintype "bidirectional"))
      (node (ref "IC2") (pin "12") (pinfunction "INPUT4_12") (pintype "input"))
      (node (ref "IC2") (pin "5") (pinfunction "INPUT1_5") (pintype "input"))
    )
    (net (code "17") (name "MISO") (class "Default")
      (node (ref "IC1") (pin "22") (pinfunction "(MISO/PCINT3)PB3_22") (pintype "bidirectional"))
      (node (ref "ICSP") (pin "1") (pinfunction "1_1") (pintype "passive"))
    )
    (net (code "18") (name "MOSI") (class "Default")
      (node (ref "IC1") (pin "21") (pinfunction "(MOSI/PCINT2)PB2_21") (pintype "bidirectional"))
      (node (ref "ICSP") (pin "4") (pinfunction "4_4") (pintype "passive"))
    )
    (net (code "19") (name "Net-(CHRG/LBO5-PadA)") (class "Default")
      (node (ref "CHRG/LBO5") (pin "A") (pinfunction "A_A") (pintype "passive"))
      (node (ref "R33") (pin "2") (pinfunction "2_2") (pintype "passive"))
    )
    (net (code "20") (name "Net-(IC1-(SCL{slash}INT0)PD0)") (class "Default")
      (node (ref "IC1") (pin "43") (pinfunction "(SCL/INT0)PD0_43") (pintype "bidirectional"))
      (node (ref "Q11") (pin "3") (pinfunction "D_3") (pintype "passive"))
      (node (ref "R24") (pin "1") (pinfunction "1_1") (pintype "passive"))
    )
    (net (code "21") (name "Net-(IC1-(SDA{slash}INT1)PD1)") (class "Default")
      (node (ref "IC1") (pin "44") (pinfunction "(SDA/INT1)PD1_44") (pintype "bidirectional"))
      (node (ref "Q12") (pin "3") (pinfunction "D_3") (pintype "passive"))
      (node (ref "R32") (pin "1") (pinfunction "1_1") (pintype "passive"))
    )
    (net (code "22") (name "Net-(IC1-XTAL1)") (class "Default")
      (node (ref "C19") (pin "2") (pinfunction "2_2") (pintype "passive"))
      (node (ref "IC1") (pin "34") (pinfunction "XTAL1_34") (pintype "input"))
      (node (ref "Q8") (pin "1") (pinfunction "1_1") (pintype "passive"))
    )
    (net (code "23") (name "Net-(IC1-XTAL2)") (class "Default")
      (node (ref "C22") (pin "2") (pinfunction "2_2") (pintype "passive"))
      (node (ref "IC1") (pin "33") (pinfunction "XTAL2_33") (pintype "output"))
      (node (ref "Q8") (pin "2") (pinfunction "2_2") (pintype "passive"))
    )
    (net (code "24") (name "Net-(IC2-OUT1)") (class "Default")
      (node (ref "D1") (pin "A") (pinfunction "A_A") (pintype "passive"))
      (node (ref "D4") (pin "A") (pinfunction "A_A") (pintype "passive"))
      (node (ref "D5") (pin "C") (pinfunction "C_C") (pintype "passive"))
      (node (ref "D8") (pin "C") (pinfunction "C_C") (pintype "passive"))
      (node (ref "IC2") (pin "14") (pinfunction "OUT4_14") (pintype "output"))
      (node (ref "IC2") (pin "2") (pinfunction "OUT1_2") (pintype "output"))
      (node (ref "R4") (pin "1") (pinfunction "1_1") (pintype "passive"))
      (node (ref "SV1") (pin "2") (pinfunction "2_2") (pintype "passive"))
    )
    (net (code "25") (name "Net-(IC2-OUT2)") (class "Default")
      (node (ref "D2") (pin "A") (pinfunction "A_A") (pintype "passive"))
      (node (ref "D3") (pin "A") (pinfunction "A_A") (pintype "passive"))
      (node (ref "D6") (pin "C") (pinfunction "C_C") (pintype "passive"))
      (node (ref "D7") (pin "C") (pinfunction "C_C") (pintype "passive"))
      (node (ref "IC2") (pin "13") (pinfunction "OUT3_13") (pintype "output"))
      (node (ref "IC2") (pin "3") (pinfunction "OUT2_3") (pintype "output"))
      (node (ref "LED3") (pin "A") (pinfunction "A_A") (pintype "passive"))
      (node (ref "LED4") (pin "C") (pinfunction "C_C") (pintype "passive"))
      (node (ref "SV1") (pin "1") (pinfunction "1_1") (pintype "passive"))
    )
    (net (code "26") (name "Net-(IC3-DC)") (class "Default")
      (node (ref "IC3") (pin "1") (pinfunction "SWC_1") (pintype "passive"))
      (node (ref "IC3") (pin "7") (pinfunction "IS_7") (pintype "passive"))
      (node (ref "IC3") (pin "8") (pinfunction "DC_8") (pintype "passive"))
      (node (ref "R6") (pin "1") (pinfunction "1_1") (pintype "passive"))
    )
    (net (code "27") (name "Net-(IC3-FB)") (class "Default")
      (node (ref "IC3") (pin "5") (pinfunction "FB_5") (pintype "passive"))
      (node (ref "R7") (pin "2") (pinfunction "2_2") (pintype "passive"))
      (node (ref "R8") (pin "2") (pinfunction "2_2") (pintype "passive"))
    )
    (net (code "28") (name "Net-(IC3-SWE)") (class "Default")
      (node (ref "D10") (pin "C") (pinfunction "C_C") (pintype "passive"))
      (node (ref "IC3") (pin "2") (pinfunction "SWE_2") (pintype "passive"))
      (node (ref "L2") (pin "1") (pinfunction "1_1") (pintype "passive"))
    )
    (net (code "29") (name "Net-(IC3-TC)") (class "Default")
      (node (ref "C16") (pin "1") (pinfunction "1_1") (pintype "passive"))
      (node (ref "IC3") (pin "3") (pinfunction "TC_3") (pintype "passive"))
    )
    (net (code "30") (name "Net-(J$1-SIGNAL)") (class "Default")
      (node (ref "J$1") (pin "SIG") (pinfunction "SIGNAL_SIG") (pintype "bidirectional"))
      (node (ref "U3") (pin "ANT") (pinfunction "ANT_ANT") (pintype "bidirectional"))
    )
    (net (code "31") (name "Net-(JP1-DTR)") (class "Default")
      (node (ref "C18") (pin "2") (pinfunction "2_2") (pintype "passive"))
      (node (ref "JP1") (pin "P$1") (pinfunction "DTR_P$1") (pintype "bidirectional"))
    )
    (net (code "32") (name "Net-(L4-2)") (class "Default")
      (node (ref "L4") (pin "P$2") (pinfunction "2_P$2") (pintype "passive"))
      (node (ref "U3") (pin "DTX") (pinfunction "DTX_DTX") (pintype "output"))
    )
    (net (code "33") (name "Net-(L5-2)") (class "Default")
      (node (ref "L5") (pin "P$2") (pinfunction "2_P$2") (pintype "passive"))
      (node (ref "U3") (pin "DRX") (pinfunction "DRX_DRX") (pintype "input"))
    )
    (net (code "34") (name "Net-(L6-1)") (class "Default")
      (node (ref "L6") (pin "P$1") (pinfunction "1_P$1") (pintype "passive"))
      (node (ref "X2") (pin "1") (pinfunction "1_1") (pintype "passive"))
    )
    (net (code "35") (name "Net-(LED1-PadA)") (class "Default")
      (node (ref "LED1") (pin "A") (pinfunction "A_A") (pintype "passive"))
      (node (ref "R1") (pin "1") (pinfunction "1_1") (pintype "passive"))
    )
    (net (code "36") (name "Net-(LED2-PadA)") (class "Default")
      (node (ref "LED2") (pin "A") (pinfunction "A_A") (pintype "passive"))
      (node (ref "R2") (pin "1") (pinfunction "1_1") (pintype "passive"))
    )
    (net (code "37") (name "Net-(LED3-PadC)") (class "Default")
      (node (ref "LED3") (pin "C") (pinfunction "C_C") (pintype "passive"))
      (node (ref "LED4") (pin "A") (pinfunction "A_A") (pintype "passive"))
      (node (ref "R4") (pin "2") (pinfunction "2_2") (pintype "passive"))
    )
    (net (code "38") (name "Net-(U2-BP)") (class "Default")
      (node (ref "C7") (pin "1") (pinfunction "1_1") (pintype "passive"))
      (node (ref "U2") (pin "4") (pinfunction "BP_4") (pintype "input"))
    )
    (net (code "39") (name "Net-(U4-3V3OUT)") (class "Default")
      (node (ref "C9") (pin "1") (pinfunction "1_1") (pintype "passive"))
      (node (ref "U4") (pin "17") (pinfunction "3V3OUT_17") (pintype "output"))
      (node (ref "U4") (pin "4") (pinfunction "VCCIO_4") (pintype "power_in"))
    )
    (net (code "40") (name "Net-(U4-RXLED)") (class "Default")
      (node (ref "LED1") (pin "C") (pinfunction "C_C") (pintype "passive"))
      (node (ref "U4") (pin "22") (pinfunction "RXLED_22") (pintype "bidirectional"))
    )
    (net (code "41") (name "Net-(U4-TXLED)") (class "Default")
      (node (ref "LED2") (pin "C") (pinfunction "C_C") (pintype "passive"))
      (node (ref "U4") (pin "23") (pinfunction "TXLED_23") (pintype "bidirectional"))
    )
    (net (code "42") (name "Net-(U4-USBDM)") (class "Default")
      (node (ref "U4") (pin "16") (pinfunction "USBDM_16") (pintype "bidirectional"))
      (node (ref "X2") (pin "2") (pinfunction "2_2") (pintype "passive"))
    )
    (net (code "43") (name "Net-(U4-USBDP)") (class "Default")
      (node (ref "U4") (pin "15") (pinfunction "USBDP_15") (pintype "bidirectional"))
      (node (ref "X2") (pin "3") (pinfunction "3_3") (pintype "passive"))
    )
    (net (code "44") (name "Net-(U6-C1)") (class "Default")
      (node (ref "C12") (pin "1") (pinfunction "1_1") (pintype "passive"))
      (node (ref "U6") (pin "7") (pinfunction "C1_7") (pintype "bidirectional"))
    )
    (net (code "45") (name "Net-(U6-SETC)") (class "Default")
      (node (ref "C11") (pin "2") (pinfunction "2_2") (pintype "passive"))
      (node (ref "U6") (pin "8") (pinfunction "SETC_8") (pintype "bidirectional"))
    )
    (net (code "46") (name "Net-(U6-SETP)") (class "Default")
      (node (ref "C11") (pin "1") (pinfunction "1_1") (pintype "passive"))
      (node (ref "U6") (pin "9") (pinfunction "SETP_9") (pintype "bidirectional"))
    )
    (net (code "47") (name "Net-(X4A-KL)") (class "Default")
      (node (ref "F2") (pin "1") (pinfunction "1_1") (pintype "passive"))
      (node (ref "X4") (pin "1") (pinfunction "KL_1") (pintype "passive"))
    )
    (net (code "48") (name "POWER") (class "Default")
      (node (ref "X3") (pin "1") (pinfunction "KL_1") (pintype "passive"))
      (node (ref "X8") (pin "2") (pinfunction "KL_2") (pintype "passive"))
    )
    (net (code "49") (name "RESET1") (class "Default")
      (node (ref "C18") (pin "1") (pinfunction "1_1") (pintype "passive"))
      (node (ref "IC1") (pin "30") (pinfunction "RESET_30") (pintype "input"))
      (node (ref "ICSP") (pin "5") (pinfunction "5_5") (pintype "passive"))
      (node (ref "R16") (pin "1") (pinfunction "1_1") (pintype "passive"))
      (node (ref "S2") (pin "1") (pinfunction "1_1") (pintype "passive"))
      (node (ref "S2") (pin "2") (pinfunction "2_2") (pintype "passive"))
    )
    (net (code "50") (name "RIGHT") (class "Default")
      (node (ref "IC1") (pin "47") (pinfunction "(ICP1)PD4_47") (pintype "bidirectional"))
      (node (ref "IC2") (pin "10") (pinfunction "INPUT3_10") (pintype "input"))
      (node (ref "IC2") (pin "7") (pinfunction "INPUT2_7") (pintype "input"))
    )
    (net (code "51") (name "RTS") (class "Default")
      (node (ref "U4") (pin "3") (pinfunction "RTS_3") (pintype "bidirectional"))
    )
    (net (code "52") (name "RX") (class "Default")
      (node (ref "IC1") (pin "2") (pinfunction "(RXD0/PCIN8)PE0_2") (pintype "bidirectional"))
      (node (ref "JP1") (pin "P$3") (pinfunction "RXI_P$3") (pintype "bidirectional"))
      (node (ref "S1") (pin "6") (pinfunction "6_6") (pintype "bidirectional"))
    )
    (net (code "53") (name "RX1") (class "Default")
      (node (ref "IC1") (pin "45") (pinfunction "(RXD1/INT2)PD2_45") (pintype "bidirectional"))
      (node (ref "J203") (pin "4") (pinfunction "4_4") (pintype "passive"))
    )
    (net (code "54") (name "SCK") (class "Default")
      (node (ref "IC1") (pin "20") (pinfunction "(SCK/PCINT1)PB1_20") (pintype "bidirectional"))
      (node (ref "ICSP") (pin "3") (pinfunction "3_3") (pintype "passive"))
      (node (ref "R33") (pin "1") (pinfunction "1_1") (pintype "passive"))
    )
    (net (code "55") (name "SCL") (class "Default")
      (node (ref "Q11") (pin "2") (pinfunction "S_2") (pintype "passive"))
      (node (ref "R23") (pin "1") (pinfunction "1_1") (pintype "passive"))
      (node (ref "U6") (pin "21") (pinfunction "SCL_21") (pintype "bidirectional"))
    )
    (net (code "56") (name "SDA") (class "Default")
      (node (ref "Q12") (pin "2") (pinfunction "S_2") (pintype "passive"))
      (node (ref "R31") (pin "1") (pinfunction "1_1") (pintype "passive"))
      (node (ref "U6") (pin "24") (pinfunction "SDA_24") (pintype "bidirectional"))
    )
    (net (code "57") (name "SERVO") (class "Default")
      (node (ref "IC1") (pin "5") (pinfunction "(OC3A/AIN1)PE3_5") (pintype "bidirectional"))
      (node (ref "SV3") (pin "1") (pinfunction "1_1") (pintype "passive"))
    )
    (net (code "58") (name "SS") (class "Default")
      (node (ref "IC1") (pin "19") (pinfunction "(SS/PCINT0)PB0_19") (pintype "bidirectional"))
    )
    (net (code "59") (name "TELEM_RX") (class "Default")
      (node (ref "IC1") (pin "13") (pinfunction "PH1(TXD2)_13") (pintype "bidirectional"))
      (node (ref "L5") (pin "P$1") (pinfunction "1_P$1") (pintype "passive"))
      (node (ref "S1") (pin "4") (pinfunction "4_4") (pintype "bidirectional"))
    )
    (net (code "60") (name "TELEM_TX") (class "Default")
      (node (ref "IC1") (pin "12") (pinfunction "PH0(RXD2)_12") (pintype "bidirectional"))
      (node (ref "L4") (pin "P$1") (pinfunction "1_P$1") (pintype "passive"))
      (node (ref "S1") (pin "1") (pinfunction "1_1") (pintype "bidirectional"))
    )
    (net (code "61") (name "TX") (class "Default")
      (node (ref "IC1") (pin "3") (pinfunction "(TXD0)PE1_3") (pintype "bidirectional"))
      (node (ref "JP1") (pin "P$2") (pinfunction "TXO_P$2") (pintype "bidirectional"))
      (node (ref "S1") (pin "3") (pinfunction "3_3") (pintype "bidirectional"))
    )
    (net (code "62") (name "TX1") (class "Default")
      (node (ref "IC1") (pin "46") (pinfunction "(TXD1/INT3)PD3_46") (pintype "bidirectional"))
      (node (ref "J203") (pin "3") (pinfunction "3_3") (pintype "passive"))
    )
    (net (code "63") (name "USBRX") (class "Default")
      (node (ref "S1") (pin "5") (pinfunction "5_5") (pintype "bidirectional"))
      (node (ref "U4") (pin "1") (pinfunction "TXD_1") (pintype "output"))
      (node (ref "X6") (pin "2") (pinfunction "KL_2") (pintype "passive"))
      (node (ref "X7") (pin "1") (pinfunction "KL_1") (pintype "passive"))
    )
    (net (code "64") (name "USBTX") (class "Default")
      (node (ref "S1") (pin "2") (pinfunction "2_2") (pintype "bidirectional"))
      (node (ref "U4") (pin "5") (pinfunction "RXD_5") (pintype "input"))
      (node (ref "X1") (pin "1") (pinfunction "KL_1") (pintype "passive"))
      (node (ref "X7") (pin "2") (pinfunction "KL_2") (pintype "passive"))
    )
    (net (code "65") (name "VCC") (class "Default")
      (node (ref "C10") (pin "1") (pinfunction "1_1") (pintype "passive"))
      (node (ref "L6") (pin "P$2") (pinfunction "2_P$2") (pintype "passive"))
      (node (ref "R1") (pin "2") (pinfunction "2_2") (pintype "passive"))
      (node (ref "R2") (pin "2") (pinfunction "2_2") (pintype "passive"))
      (node (ref "U4") (pin "20") (pinfunction "VCC_20") (pintype "power_in"))
    )
    (net (code "66") (name "VIDEO") (class "Default")
      (node (ref "U$10") (pin "P$3") (pinfunction "SIGNAL_P$3") (pintype "bidirectional"))
      (node (ref "U$11") (pin "P$3") (pinfunction "SIGNAL_P$3") (pintype "bidirectional"))
      (node (ref "X10") (pin "2") (pinfunction "KL_2") (pintype "passive"))
      (node (ref "X3") (pin "2") (pinfunction "KL_2") (pintype "passive"))
    )
    (net (code "67") (name "unconnected-(IC1-(A8)PC0-Pad53)") (class "Default")
      (node (ref "IC1") (pin "53") (pinfunction "(A8)PC0_53") (pintype "bidirectional"))
    )
    (net (code "68") (name "unconnected-(IC1-(A9)PC1-Pad54)") (class "Default")
      (node (ref "IC1") (pin "54") (pinfunction "(A9)PC1_54") (pintype "bidirectional"))
    )
    (net (code "69") (name "unconnected-(IC1-(A10)PC2-Pad55)") (class "Default")
      (node (ref "IC1") (pin "55") (pinfunction "(A10)PC2_55") (pintype "bidirectional"))
    )
    (net (code "70") (name "unconnected-(IC1-(A11)PC3-Pad56)") (class "Default")
      (node (ref "IC1") (pin "56") (pinfunction "(A11)PC3_56") (pintype "bidirectional"))
    )
    (net (code "71") (name "unconnected-(IC1-(A12)PC4-Pad57)") (class "Default")
      (node (ref "IC1") (pin "57") (pinfunction "(A12)PC4_57") (pintype "bidirectional"))
    )
    (net (code "72") (name "unconnected-(IC1-(A13)PC5-Pad58)") (class "Default")
      (node (ref "IC1") (pin "58") (pinfunction "(A13)PC5_58") (pintype "bidirectional"))
    )
    (net (code "73") (name "unconnected-(IC1-(AD0)PA0-Pad78)") (class "Default")
      (node (ref "IC1") (pin "78") (pinfunction "(AD0)PA0_78") (pintype "bidirectional"))
    )
    (net (code "74") (name "unconnected-(IC1-(AD1)PA1-Pad77)") (class "Default")
      (node (ref "IC1") (pin "77") (pinfunction "(AD1)PA1_77") (pintype "bidirectional"))
    )
    (net (code "75") (name "unconnected-(IC1-(AD2)PA2-Pad76)") (class "Default")
      (node (ref "IC1") (pin "76") (pinfunction "(AD2)PA2_76") (pintype "bidirectional"))
    )
    (net (code "76") (name "unconnected-(IC1-(AD3)PA3-Pad75)") (class "Default")
      (node (ref "IC1") (pin "75") (pinfunction "(AD3)PA3_75") (pintype "bidirectional"))
    )
    (net (code "77") (name "unconnected-(IC1-(AD4)PA4-Pad74)") (class "Default")
      (node (ref "IC1") (pin "74") (pinfunction "(AD4)PA4_74") (pintype "bidirectional"))
    )
    (net (code "78") (name "unconnected-(IC1-(AD5)PA5-Pad73)") (class "Default")
      (node (ref "IC1") (pin "73") (pinfunction "(AD5)PA5_73") (pintype "bidirectional"))
    )
    (net (code "79") (name "unconnected-(IC1-(AD6)PA6-Pad72)") (class "Default")
      (node (ref "IC1") (pin "72") (pinfunction "(AD6)PA6_72") (pintype "bidirectional"))
    )
    (net (code "80") (name "unconnected-(IC1-(AD7)PA7-Pad71)") (class "Default")
      (node (ref "IC1") (pin "71") (pinfunction "(AD7)PA7_71") (pintype "bidirectional"))
    )
    (net (code "81") (name "unconnected-(IC1-(ADC0)PF0-Pad97)") (class "Default")
      (node (ref "IC1") (pin "97") (pinfunction "(ADC0)PF0_97") (pintype "bidirectional"))
    )
    (net (code "82") (name "unconnected-(IC1-(ADC1)PF1-Pad96)") (class "Default")
      (node (ref "IC1") (pin "96") (pinfunction "(ADC1)PF1_96") (pintype "bidirectional"))
    )
    (net (code "83") (name "unconnected-(IC1-(ADC2)PF2-Pad95)") (class "Default")
      (node (ref "IC1") (pin "95") (pinfunction "(ADC2)PF2_95") (pintype "bidirectional"))
    )
    (net (code "84") (name "unconnected-(IC1-(ADC3)PF3-Pad94)") (class "Default")
      (node (ref "IC1") (pin "94") (pinfunction "(ADC3)PF3_94") (pintype "bidirectional"))
    )
    (net (code "85") (name "unconnected-(IC1-(ADC4{slash}TCK)PF4-Pad93)") (class "Default")
      (node (ref "IC1") (pin "93") (pinfunction "(ADC4/TCK)PF4_93") (pintype "bidirectional"))
    )
    (net (code "86") (name "unconnected-(IC1-(ADC5{slash}TMS)PF5-Pad92)") (class "Default")
      (node (ref "IC1") (pin "92") (pinfunction "(ADC5/TMS)PF5_92") (pintype "bidirectional"))
    )
    (net (code "87") (name "unconnected-(IC1-(ADC6{slash}TDO)PF6-Pad91)") (class "Default")
      (node (ref "IC1") (pin "91") (pinfunction "(ADC6/TDO)PF6_91") (pintype "bidirectional"))
    )
    (net (code "88") (name "unconnected-(IC1-(ADC7{slash}TDI)PF7-Pad90)") (class "Default")
      (node (ref "IC1") (pin "90") (pinfunction "(ADC7/TDI)PF7_90") (pintype "bidirectional"))
    )
    (net (code "89") (name "unconnected-(IC1-(ALE)PG2-Pad70)") (class "Default")
      (node (ref "IC1") (pin "70") (pinfunction "(ALE)PG2_70") (pintype "bidirectional"))
    )
    (net (code "90") (name "unconnected-(IC1-(CLKO{slash}ICP3{slash}INT7)PE7-Pad9)") (class "Default")
      (node (ref "IC1") (pin "9") (pinfunction "(CLKO/ICP3/INT7)PE7_9") (pintype "bidirectional"))
    )
    (net (code "91") (name "unconnected-(IC1-(OC0A{slash}OC1C{slash}PCINT7)PB7-Pad26)") (class "Default")
      (node (ref "IC1") (pin "26") (pinfunction "(OC0A/OC1C/PCINT7)PB7_26") (pintype "bidirectional"))
    )
    (net (code "92") (name "unconnected-(IC1-(OC1A{slash}PCINT5)PB5-Pad24)") (class "Default")
      (node (ref "IC1") (pin "24") (pinfunction "(OC1A/PCINT5)PB5_24") (pintype "bidirectional"))
    )
    (net (code "93") (name "unconnected-(IC1-(OC1B{slash}PCINT6)PB6-Pad25)") (class "Default")
      (node (ref "IC1") (pin "25") (pinfunction "(OC1B/PCINT6)PB6_25") (pintype "bidirectional"))
    )
    (net (code "94") (name "unconnected-(IC1-(OC2A{slash}PCINT4)PB4-Pad23)") (class "Default")
      (node (ref "IC1") (pin "23") (pinfunction "(OC2A/PCINT4)PB4_23") (pintype "bidirectional"))
    )
    (net (code "95") (name "unconnected-(IC1-(OC3B{slash}INT4)PE4-Pad6)") (class "Default")
      (node (ref "IC1") (pin "6") (pinfunction "(OC3B/INT4)PE4_6") (pintype "bidirectional"))
    )
    (net (code "96") (name "unconnected-(IC1-(OC3C{slash}INT5)PE5-Pad7)") (class "Default")
      (node (ref "IC1") (pin "7") (pinfunction "(OC3C/INT5)PE5_7") (pintype "bidirectional"))
    )
    (net (code "97") (name "unconnected-(IC1-(RD)PG1-Pad52)") (class "Default")
      (node (ref "IC1") (pin "52") (pinfunction "(RD)PG1_52") (pintype "bidirectional"))
    )
    (net (code "98") (name "unconnected-(IC1-(T0)PD7-Pad50)") (class "Default")
      (node (ref "IC1") (pin "50") (pinfunction "(T0)PD7_50") (pintype "bidirectional"))
    )
    (net (code "99") (name "unconnected-(IC1-(T1)PD6-Pad49)") (class "Default")
      (node (ref "IC1") (pin "49") (pinfunction "(T1)PD6_49") (pintype "bidirectional"))
    )
    (net (code "100") (name "unconnected-(IC1-(T3{slash}INT6)PE6-Pad8)") (class "Default")
      (node (ref "IC1") (pin "8") (pinfunction "(T3/INT6)PE6_8") (pintype "bidirectional"))
    )
    (net (code "101") (name "unconnected-(IC1-(TOSC1)PG4-Pad29)") (class "Default")
      (node (ref "IC1") (pin "29") (pinfunction "(TOSC1)PG4_29") (pintype "bidirectional"))
    )
    (net (code "102") (name "unconnected-(IC1-(TOSC2)PG3-Pad28)") (class "Default")
      (node (ref "IC1") (pin "28") (pinfunction "(TOSC2)PG3_28") (pintype "bidirectional"))
    )
    (net (code "103") (name "unconnected-(IC1-(WR)PG0-Pad51)") (class "Default")
      (node (ref "IC1") (pin "51") (pinfunction "(WR)PG0_51") (pintype "bidirectional"))
    )
    (net (code "104") (name "unconnected-(IC1-(XCK0{slash}AIN0)PE2-Pad4)") (class "Default")
      (node (ref "IC1") (pin "4") (pinfunction "(XCK0/AIN0)PE2_4") (pintype "bidirectional"))
    )
    (net (code "105") (name "unconnected-(IC1-AREF-Pad98)") (class "Default")
      (node (ref "IC1") (pin "98") (pinfunction "AREF_98") (pintype "bidirectional"))
    )
    (net (code "106") (name "unconnected-(IC1-PH2(XCK2)-Pad14)") (class "Default")
      (node (ref "IC1") (pin "14") (pinfunction "PH2(XCK2)_14") (pintype "bidirectional"))
    )
    (net (code "107") (name "unconnected-(IC1-PH3(OC4A)-Pad15)") (class "Default")
      (node (ref "IC1") (pin "15") (pinfunction "PH3(OC4A)_15") (pintype "bidirectional"))
    )
    (net (code "108") (name "unconnected-(IC1-PH4(OC4B)-Pad16)") (class "Default")
      (node (ref "IC1") (pin "16") (pinfunction "PH4(OC4B)_16") (pintype "bidirectional"))
    )
    (net (code "109") (name "unconnected-(IC1-PH5(OC4C)-Pad17)") (class "Default")
      (node (ref "IC1") (pin "17") (pinfunction "PH5(OC4C)_17") (pintype "bidirectional"))
    )
    (net (code "110") (name "unconnected-(IC1-PH6(OC2B)-Pad18)") (class "Default")
      (node (ref "IC1") (pin "18") (pinfunction "PH6(OC2B)_18") (pintype "bidirectional"))
    )
    (net (code "111") (name "unconnected-(IC1-PH7(T4)-Pad27)") (class "Default")
      (node (ref "IC1") (pin "27") (pinfunction "PH7(T4)_27") (pintype "bidirectional"))
    )
    (net (code "112") (name "unconnected-(IC1-PJ0(RXD3{slash}PCINT9)-Pad63)") (class "Default")
      (node (ref "IC1") (pin "63") (pinfunction "PJ0(RXD3/PCINT9)_63") (pintype "bidirectional"))
    )
    (net (code "113") (name "unconnected-(IC1-PJ1(TXD3{slash}PCINT10)-Pad64)") (class "Default")
      (node (ref "IC1") (pin "64") (pinfunction "PJ1(TXD3/PCINT10)_64") (pintype "bidirectional"))
    )
    (net (code "114") (name "unconnected-(IC1-PJ2(XCK3{slash}PCINT11)-Pad65)") (class "Default")
      (node (ref "IC1") (pin "65") (pinfunction "PJ2(XCK3/PCINT11)_65") (pintype "bidirectional"))
    )
    (net (code "115") (name "unconnected-(IC1-PJ3(PCINT12)-Pad66)") (class "Default")
      (node (ref "IC1") (pin "66") (pinfunction "PJ3(PCINT12)_66") (pintype "bidirectional"))
    )
    (net (code "116") (name "unconnected-(IC1-PJ4(PCINT13)-Pad67)") (class "Default")
      (node (ref "IC1") (pin "67") (pinfunction "PJ4(PCINT13)_67") (pintype "bidirectional"))
    )
    (net (code "117") (name "unconnected-(IC1-PJ5(PCINT14)-Pad68)") (class "Default")
      (node (ref "IC1") (pin "68") (pinfunction "PJ5(PCINT14)_68") (pintype "bidirectional"))
    )
    (net (code "118") (name "unconnected-(IC1-PJ6(PCINT15)-Pad69)") (class "Default")
      (node (ref "IC1") (pin "69") (pinfunction "PJ6(PCINT15)_69") (pintype "bidirectional"))
    )
    (net (code "119") (name "unconnected-(IC1-PJ7-Pad79)") (class "Default")
      (node (ref "IC1") (pin "79") (pinfunction "PJ7_79") (pintype "bidirectional"))
    )
    (net (code "120") (name "unconnected-(IC1-PK0(ADC8{slash}PCINT16)-Pad89)") (class "Default")
      (node (ref "IC1") (pin "89") (pinfunction "PK0(ADC8/PCINT16)_89") (pintype "bidirectional"))
    )
    (net (code "121") (name "unconnected-(IC1-PK1(ADC9{slash}PCINT17)-Pad88)") (class "Default")
      (node (ref "IC1") (pin "88") (pinfunction "PK1(ADC9/PCINT17)_88") (pintype "bidirectional"))
    )
    (net (code "122") (name "unconnected-(IC1-PK2(ADC10{slash}PCINT18)-Pad87)") (class "Default")
      (node (ref "IC1") (pin "87") (pinfunction "PK2(ADC10/PCINT18)_87") (pintype "bidirectional"))
    )
    (net (code "123") (name "unconnected-(IC1-PK3(ADC11{slash}PCINT19)-Pad86)") (class "Default")
      (node (ref "IC1") (pin "86") (pinfunction "PK3(ADC11/PCINT19)_86") (pintype "bidirectional"))
    )
    (net (code "124") (name "unconnected-(IC1-PK4(ADC12{slash}PCINT20)-Pad85)") (class "Default")
      (node (ref "IC1") (pin "85") (pinfunction "PK4(ADC12/PCINT20)_85") (pintype "bidirectional"))
    )
    (net (code "125") (name "unconnected-(IC1-PK5(ADC13{slash}PCINT21)-Pad84)") (class "Default")
      (node (ref "IC1") (pin "84") (pinfunction "PK5(ADC13/PCINT21)_84") (pintype "bidirectional"))
    )
    (net (code "126") (name "unconnected-(IC1-PK6(ADC14{slash}PCINT22)-Pad83)") (class "Default")
      (node (ref "IC1") (pin "83") (pinfunction "PK6(ADC14/PCINT22)_83") (pintype "bidirectional"))
    )
    (net (code "127") (name "unconnected-(IC1-PK7(ADC15{slash}PCINT23)-Pad82)") (class "Default")
      (node (ref "IC1") (pin "82") (pinfunction "PK7(ADC15/PCINT23)_82") (pintype "bidirectional"))
    )
    (net (code "128") (name "unconnected-(IC1-PL0(ICP4)-Pad35)") (class "Default")
      (node (ref "IC1") (pin "35") (pinfunction "PL0(ICP4)_35") (pintype "bidirectional"))
    )
    (net (code "129") (name "unconnected-(IC1-PL1(ICP5)-Pad36)") (class "Default")
      (node (ref "IC1") (pin "36") (pinfunction "PL1(ICP5)_36") (pintype "bidirectional"))
    )
    (net (code "130") (name "unconnected-(IC1-PL2(T5)-Pad37)") (class "Default")
      (node (ref "IC1") (pin "37") (pinfunction "PL2(T5)_37") (pintype "bidirectional"))
    )
    (net (code "131") (name "unconnected-(IC1-PL3(OC5A)-Pad38)") (class "Default")
      (node (ref "IC1") (pin "38") (pinfunction "PL3(OC5A)_38") (pintype "bidirectional"))
    )
    (net (code "132") (name "unconnected-(IC1-PL4(OC5B)-Pad39)") (class "Default")
      (node (ref "IC1") (pin "39") (pinfunction "PL4(OC5B)_39") (pintype "bidirectional"))
    )
    (net (code "133") (name "unconnected-(IC1-PL5(OC5C)-Pad40)") (class "Default")
      (node (ref "IC1") (pin "40") (pinfunction "PL5(OC5C)_40") (pintype "bidirectional"))
    )
    (net (code "134") (name "unconnected-(IC1-PL6-Pad41)") (class "Default")
      (node (ref "IC1") (pin "41") (pinfunction "PL6_41") (pintype "bidirectional"))
    )
    (net (code "135") (name "unconnected-(IC1-PL7-Pad42)") (class "Default")
      (node (ref "IC1") (pin "42") (pinfunction "PL7_42") (pintype "bidirectional"))
    )
    (net (code "136") (name "unconnected-(IC2-SEN_A-Pad1)") (class "Default")
      (node (ref "IC2") (pin "1") (pinfunction "SEN_A_1") (pintype "input"))
    )
    (net (code "137") (name "unconnected-(IC2-SEN_B-Pad15)") (class "Default")
      (node (ref "IC2") (pin "15") (pinfunction "SEN_B_15") (pintype "input"))
    )
    (net (code "138") (name "unconnected-(J203-Pad6)") (class "Default")
      (node (ref "J203") (pin "6") (pinfunction "6_6") (pintype "passive"))
    )
    (net (code "139") (name "unconnected-(U3-PadTEST)") (class "Default")
      (node (ref "U3") (pin "TEST") (pinfunction "TEST_TEST") (pintype "no_connect"))
    )
  )
)
